# 10_FE_LANPORT.net
KiCad netlist of a schematic drawn in Altium Designer
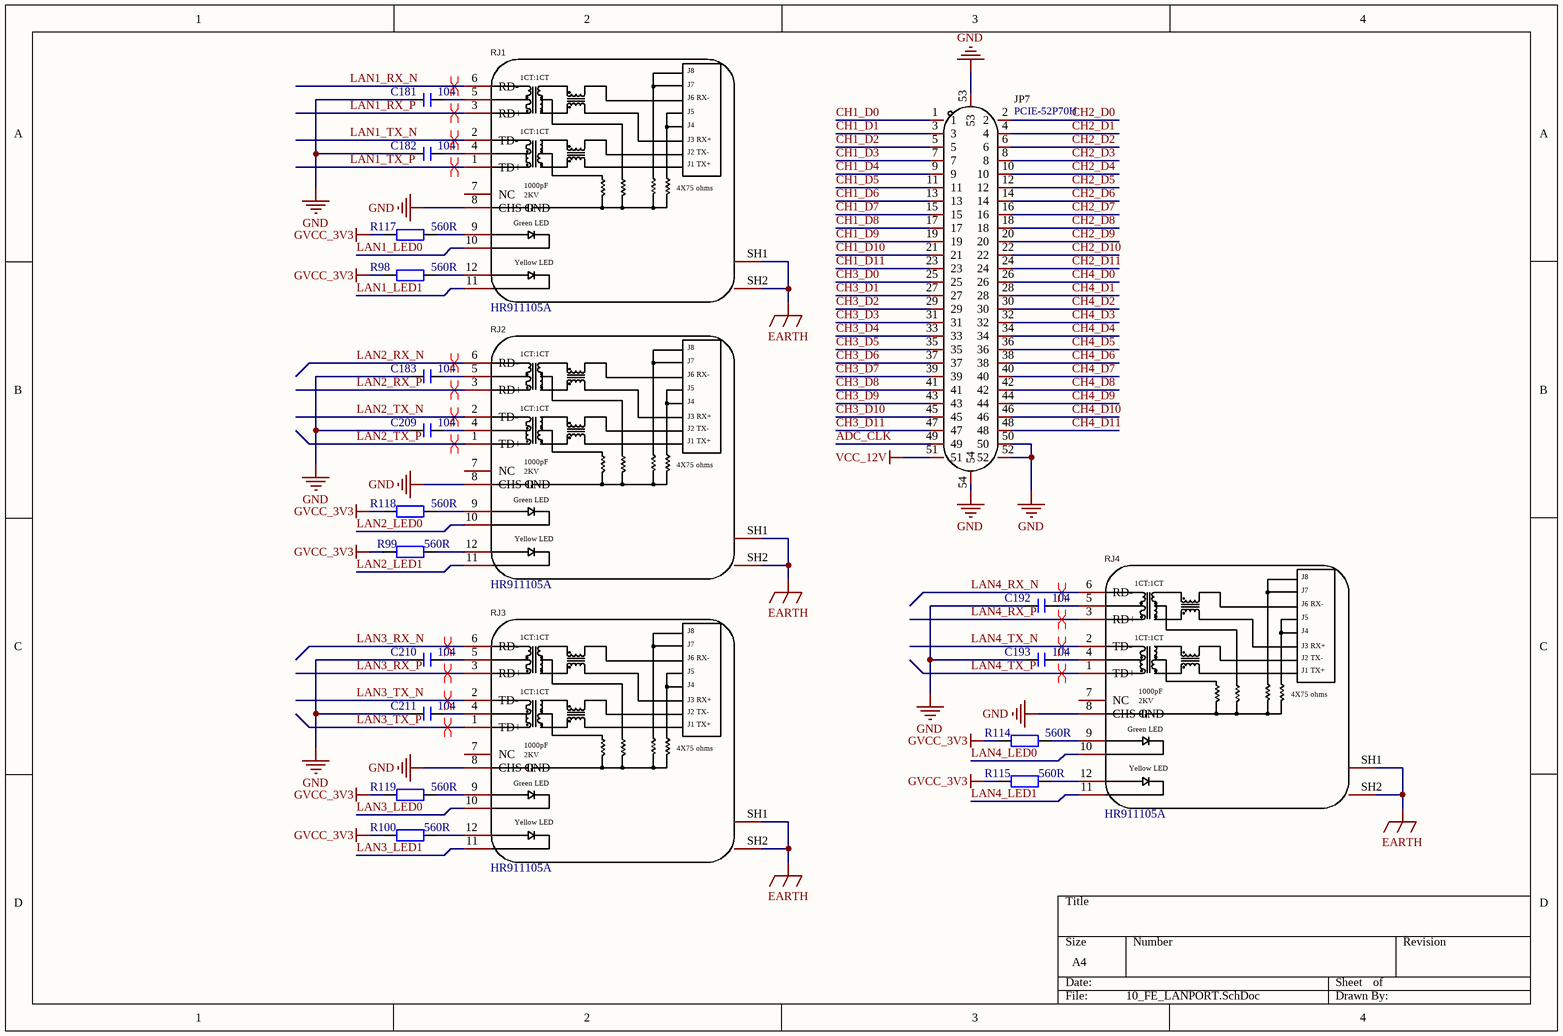
[diagram p0: 10_FE_LANPORT.SchDoc]

(export (version "E")
  (design (tool "Eeschema 10.0.6"))
  (components
    (comp (ref "C181")
      (value "104")
      (footprint "C 0603")
      (description "无极性贴片电容")
      (fields (field (name "版权归属") "源创客"))
      (libsource (lib "STM32MP15x底板封装库V1.4") (part "C"))
    )
    (comp (ref "C182")
      (value "104")
      (footprint "C 0603")
      (description "无极性贴片电容")
      (fields (field (name "版权归属") "源创客"))
      (libsource (lib "STM32MP15x底板封装库V1.4") (part "C"))
    )
    (comp (ref "C183")
      (value "104")
      (footprint "C 0603")
      (description "无极性贴片电容")
      (fields (field (name "版权归属") "源创客"))
      (libsource (lib "STM32MP15x底板封装库V1.4") (part "C"))
    )
    (comp (ref "C192")
      (value "104")
      (footprint "C 0603")
      (description "无极性贴片电容")
      (fields (field (name "版权归属") "源创客"))
      (libsource (lib "STM32MP15x底板封装库V1.4") (part "C"))
    )
    (comp (ref "C193")
      (value "104")
      (footprint "C 0603")
      (description "无极性贴片电容")
      (fields (field (name "版权归属") "源创客"))
      (libsource (lib "STM32MP15x底板封装库V1.4") (part "C"))
    )
    (comp (ref "C209")
      (value "104")
      (footprint "C 0603")
      (description "无极性贴片电容")
      (fields (field (name "版权归属") "源创客"))
      (libsource (lib "STM32MP15x底板封装库V1.4") (part "C"))
    )
    (comp (ref "C210")
      (value "104")
      (footprint "C 0603")
      (description "无极性贴片电容")
      (fields (field (name "版权归属") "源创客"))
      (libsource (lib "STM32MP15x底板封装库V1.4") (part "C"))
    )
    (comp (ref "C211")
      (value "104")
      (footprint "C 0603")
      (description "无极性贴片电容")
      (fields (field (name "版权归属") "源创客"))
      (libsource (lib "STM32MP15x底板封装库V1.4") (part "C"))
    )
    (comp (ref "JP7")
      (value "PCIE-52P70H")
      (footprint "MINI PCIe")
      (fields (field (name "MANUFACTURER") "XUNPU(讯普)"))
      (libsource (lib "PCIE-52P70H") (part "PCIE-52P70H"))
    )
    (comp (ref "R98")
      (value "560R")
      (footprint "R 0603")
      (description "贴片电阻")
      (fields (field (name "版权归属") "源创客"))
      (libsource (lib "STM32MP15x底板封装库V1.4") (part "R"))
    )
    (comp (ref "R99")
      (value "560R")
      (footprint "R 0603")
      (description "贴片电阻")
      (fields (field (name "版权归属") "源创客"))
      (libsource (lib "STM32MP15x底板封装库V1.4") (part "R"))
    )
    (comp (ref "R100")
      (value "560R")
      (footprint "R 0603")
      (description "贴片电阻")
      (fields (field (name "版权归属") "源创客"))
      (libsource (lib "STM32MP15x底板封装库V1.4") (part "R"))
    )
    (comp (ref "R114")
      (value "560R")
      (footprint "R 0603")
      (description "贴片电阻")
      (fields (field (name "版权归属") "源创客"))
      (libsource (lib "STM32MP15x底板封装库V1.4") (part "R"))
    )
    (comp (ref "R115")
      (value "560R")
      (footprint "R 0603")
      (description "贴片电阻")
      (fields (field (name "版权归属") "源创客"))
      (libsource (lib "STM32MP15x底板封装库V1.4") (part "R"))
    )
    (comp (ref "R117")
      (value "560R")
      (footprint "R 0603")
      (description "贴片电阻")
      (fields (field (name "版权归属") "源创客"))
      (libsource (lib "STM32MP15x底板封装库V1.4") (part "R"))
    )
    (comp (ref "R118")
      (value "560R")
      (footprint "R 0603")
      (description "贴片电阻")
      (fields (field (name "版权归属") "源创客"))
      (libsource (lib "STM32MP15x底板封装库V1.4") (part "R"))
    )
    (comp (ref "R119")
      (value "560R")
      (footprint "R 0603")
      (description "贴片电阻")
      (fields (field (name "版权归属") "源创客"))
      (libsource (lib "STM32MP15x底板封装库V1.4") (part "R"))
    )
    (comp (ref "RJ1")
      (value "HR911105A")
      (footprint "HR91105A")
      (fields (field (name "MANUFACTURER") "HANRUN(汉仁)"))
      (libsource (lib "HR911105A") (part "HR911105A"))
    )
    (comp (ref "RJ2")
      (value "HR911105A")
      (footprint "HR91105A")
      (fields (field (name "MANUFACTURER") "HANRUN(汉仁)"))
      (libsource (lib "HR911105A") (part "HR911105A"))
    )
    (comp (ref "RJ3")
      (value "HR911105A")
      (footprint "HR91105A")
      (fields (field (name "MANUFACTURER") "HANRUN(汉仁)"))
      (libsource (lib "HR911105A") (part "HR911105A"))
    )
    (comp (ref "RJ4")
      (value "HR911105A")
      (footprint "HR91105A")
      (fields (field (name "MANUFACTURER") "HANRUN(汉仁)"))
      (libsource (lib "HR911105A") (part "HR911105A"))
    )
  )
  (nets
    (net (code "1") (name "/ADC_CLK") (class "Default")
      (node (ref "JP7") (pin "49") (pinfunction "49_49") (pintype "passive"))
    )
    (net (code "2") (name "/CH1_D0") (class "Default")
      (node (ref "JP7") (pin "1") (pinfunction "1_1") (pintype "passive"))
    )
    (net (code "3") (name "/CH1_D1") (class "Default")
      (node (ref "JP7") (pin "3") (pinfunction "3_3") (pintype "passive"))
    )
    (net (code "4") (name "/CH1_D2") (class "Default")
      (node (ref "JP7") (pin "5") (pinfunction "5_5") (pintype "passive"))
    )
    (net (code "5") (name "/CH1_D3") (class "Default")
      (node (ref "JP7") (pin "7") (pinfunction "7_7") (pintype "passive"))
    )
    (net (code "6") (name "/CH1_D4") (class "Default")
      (node (ref "JP7") (pin "9") (pinfunction "9_9") (pintype "passive"))
    )
    (net (code "7") (name "/CH1_D5") (class "Default")
      (node (ref "JP7") (pin "11") (pinfunction "11_11") (pintype "passive"))
    )
    (net (code "8") (name "/CH1_D6") (class "Default")
      (node (ref "JP7") (pin "13") (pinfunction "13_13") (pintype "passive"))
    )
    (net (code "9") (name "/CH1_D7") (class "Default")
      (node (ref "JP7") (pin "15") (pinfunction "15_15") (pintype "passive"))
    )
    (net (code "10") (name "/CH1_D8") (class "Default")
      (node (ref "JP7") (pin "17") (pinfunction "17_17") (pintype "passive"))
    )
    (net (code "11") (name "/CH1_D9") (class "Default")
      (node (ref "JP7") (pin "19") (pinfunction "19_19") (pintype "passive"))
    )
    (net (code "12") (name "/CH1_D10") (class "Default")
      (node (ref "JP7") (pin "21") (pinfunction "21_21") (pintype "passive"))
    )
    (net (code "13") (name "/CH1_D11") (class "Default")
      (node (ref "JP7") (pin "23") (pinfunction "23_23") (pintype "passive"))
    )
    (net (code "14") (name "/CH2_D0") (class "Default")
      (node (ref "JP7") (pin "2") (pinfunction "2_2") (pintype "passive"))
    )
    (net (code "15") (name "/CH2_D1") (class "Default")
      (node (ref "JP7") (pin "4") (pinfunction "4_4") (pintype "passive"))
    )
    (net (code "16") (name "/CH2_D2") (class "Default")
      (node (ref "JP7") (pin "6") (pinfunction "6_6") (pintype "passive"))
    )
    (net (code "17") (name "/CH2_D3") (class "Default")
      (node (ref "JP7") (pin "8") (pinfunction "8_8") (pintype "passive"))
    )
    (net (code "18") (name "/CH2_D4") (class "Default")
      (node (ref "JP7") (pin "10") (pinfunction "10_10") (pintype "passive"))
    )
    (net (code "19") (name "/CH2_D5") (class "Default")
      (node (ref "JP7") (pin "12") (pinfunction "12_12") (pintype "passive"))
    )
    (net (code "20") (name "/CH2_D6") (class "Default")
      (node (ref "JP7") (pin "14") (pinfunction "14_14") (pintype "passive"))
    )
    (net (code "21") (name "/CH2_D7") (class "Default")
      (node (ref "JP7") (pin "16") (pinfunction "16_16") (pintype "passive"))
    )
    (net (code "22") (name "/CH2_D8") (class "Default")
      (node (ref "JP7") (pin "18") (pinfunction "18_18") (pintype "passive"))
    )
    (net (code "23") (name "/CH2_D9") (class "Default")
      (node (ref "JP7") (pin "20") (pinfunction "20_20") (pintype "passive"))
    )
    (net (code "24") (name "/CH2_D10") (class "Default")
      (node (ref "JP7") (pin "22") (pinfunction "22_22") (pintype "passive"))
    )
    (net (code "25") (name "/CH2_D11") (class "Default")
      (node (ref "JP7") (pin "24") (pinfunction "24_24") (pintype "passive"))
    )
    (net (code "26") (name "/CH3_D0") (class "Default")
      (node (ref "JP7") (pin "25") (pinfunction "25_25") (pintype "passive"))
    )
    (net (code "27") (name "/CH3_D1") (class "Default")
      (node (ref "JP7") (pin "27") (pinfunction "27_27") (pintype "passive"))
    )
    (net (code "28") (name "/CH3_D2") (class "Default")
      (node (ref "JP7") (pin "29") (pinfunction "29_29") (pintype "passive"))
    )
    (net (code "29") (name "/CH3_D3") (class "Default")
      (node (ref "JP7") (pin "31") (pinfunction "31_31") (pintype "passive"))
    )
    (net (code "30") (name "/CH3_D4") (class "Default")
      (node (ref "JP7") (pin "33") (pinfunction "33_33") (pintype "passive"))
    )
    (net (code "31") (name "/CH3_D5") (class "Default")
      (node (ref "JP7") (pin "35") (pinfunction "35_35") (pintype "passive"))
    )
    (net (code "32") (name "/CH3_D6") (class "Default")
      (node (ref "JP7") (pin "37") (pinfunction "37_37") (pintype "passive"))
    )
    (net (code "33") (name "/CH3_D7") (class "Default")
      (node (ref "JP7") (pin "39") (pinfunction "39_39") (pintype "passive"))
    )
    (net (code "34") (name "/CH3_D8") (class "Default")
      (node (ref "JP7") (pin "41") (pinfunction "41_41") (pintype "passive"))
    )
    (net (code "35") (name "/CH3_D9") (class "Default")
      (node (ref "JP7") (pin "43") (pinfunction "43_43") (pintype "passive"))
    )
    (net (code "36") (name "/CH3_D10") (class "Default")
      (node (ref "JP7") (pin "45") (pinfunction "45_45") (pintype "passive"))
    )
    (net (code "37") (name "/CH3_D11") (class "Default")
      (node (ref "JP7") (pin "47") (pinfunction "47_47") (pintype "passive"))
    )
    (net (code "38") (name "/CH4_D0") (class "Default")
      (node (ref "JP7") (pin "26") (pinfunction "26_26") (pintype "passive"))
    )
    (net (code "39") (name "/CH4_D1") (class "Default")
      (node (ref "JP7") (pin "28") (pinfunction "28_28") (pintype "passive"))
    )
    (net (code "40") (name "/CH4_D2") (class "Default")
      (node (ref "JP7") (pin "30") (pinfunction "30_30") (pintype "passive"))
    )
    (net (code "41") (name "/CH4_D3") (class "Default")
      (node (ref "JP7") (pin "32") (pinfunction "32_32") (pintype "passive"))
    )
    (net (code "42") (name "/CH4_D4") (class "Default")
      (node (ref "JP7") (pin "34") (pinfunction "34_34") (pintype "passive"))
    )
    (net (code "43") (name "/CH4_D5") (class "Default")
      (node (ref "JP7") (pin "36") (pinfunction "36_36") (pintype "passive"))
    )
    (net (code "44") (name "/CH4_D6") (class "Default")
      (node (ref "JP7") (pin "38") (pinfunction "38_38") (pintype "passive"))
    )
    (net (code "45") (name "/CH4_D7") (class "Default")
      (node (ref "JP7") (pin "40") (pinfunction "40_40") (pintype "passive"))
    )
    (net (code "46") (name "/CH4_D8") (class "Default")
      (node (ref "JP7") (pin "42") (pinfunction "42_42") (pintype "passive"))
    )
    (net (code "47") (name "/CH4_D9") (class "Default")
      (node (ref "JP7") (pin "44") (pinfunction "44_44") (pintype "passive"))
    )
    (net (code "48") (name "/CH4_D10") (class "Default")
      (node (ref "JP7") (pin "46") (pinfunction "46_46") (pintype "passive"))
    )
    (net (code "49") (name "/CH4_D11") (class "Default")
      (node (ref "JP7") (pin "48") (pinfunction "48_48") (pintype "passive"))
    )
    (net (code "50") (name "/LAN1_LED0") (class "Default")
      (node (ref "RJ1") (pin "10") (pinfunction "10_10") (pintype "passive"))
    )
    (net (code "51") (name "/LAN1_LED1") (class "Default")
      (node (ref "RJ1") (pin "11") (pinfunction "11_11") (pintype "passive"))
    )
    (net (code "52") (name "/LAN1_RX_N") (class "Default")
      (node (ref "RJ1") (pin "6") (pinfunction "RD-_6") (pintype "passive"))
    )
    (net (code "53") (name "/LAN1_RX_P") (class "Default")
      (node (ref "RJ1") (pin "3") (pinfunction "RD+_3") (pintype "passive"))
    )
    (net (code "54") (name "/LAN1_TX_N") (class "Default")
      (node (ref "RJ1") (pin "2") (pinfunction "TD-_2") (pintype "passive"))
    )
    (net (code "55") (name "/LAN1_TX_P") (class "Default")
      (node (ref "RJ1") (pin "1") (pinfunction "TD+_1") (pintype "passive"))
    )
    (net (code "56") (name "/LAN2_LED0") (class "Default")
      (node (ref "RJ2") (pin "10") (pinfunction "10_10") (pintype "passive"))
    )
    (net (code "57") (name "/LAN2_LED1") (class "Default")
      (node (ref "RJ2") (pin "11") (pinfunction "11_11") (pintype "passive"))
    )
    (net (code "58") (name "/LAN2_RX_N") (class "Default")
      (node (ref "RJ2") (pin "6") (pinfunction "RD-_6") (pintype "passive"))
    )
    (net (code "59") (name "/LAN2_RX_P") (class "Default")
      (node (ref "RJ2") (pin "3") (pinfunction "RD+_3") (pintype "passive"))
    )
    (net (code "60") (name "/LAN2_TX_N") (class "Default")
      (node (ref "RJ2") (pin "2") (pinfunction "TD-_2") (pintype "passive"))
    )
    (net (code "61") (name "/LAN2_TX_P") (class "Default")
      (node (ref "RJ2") (pin "1") (pinfunction "TD+_1") (pintype "passive"))
    )
    (net (code "62") (name "/LAN3_LED0") (class "Default")
      (node (ref "RJ3") (pin "10") (pinfunction "10_10") (pintype "passive"))
    )
    (net (code "63") (name "/LAN3_LED1") (class "Default")
      (node (ref "RJ3") (pin "11") (pinfunction "11_11") (pintype "passive"))
    )
    (net (code "64") (name "/LAN3_RX_N") (class "Default")
      (node (ref "RJ3") (pin "6") (pinfunction "RD-_6") (pintype "passive"))
    )
    (net (code "65") (name "/LAN3_RX_P") (class "Default")
      (node (ref "RJ3") (pin "3") (pinfunction "RD+_3") (pintype "passive"))
    )
    (net (code "66") (name "/LAN3_TX_N") (class "Default")
      (node (ref "RJ3") (pin "2") (pinfunction "TD-_2") (pintype "passive"))
    )
    (net (code "67") (name "/LAN3_TX_P") (class "Default")
      (node (ref "RJ3") (pin "1") (pinfunction "TD+_1") (pintype "passive"))
    )
    (net (code "68") (name "/LAN4_LED0") (class "Default")
      (node (ref "RJ4") (pin "10") (pinfunction "10_10") (pintype "passive"))
    )
    (net (code "69") (name "/LAN4_LED1") (class "Default")
      (node (ref "RJ4") (pin "11") (pinfunction "11_11") (pintype "passive"))
    )
    (net (code "70") (name "/LAN4_RX_N") (class "Default")
      (node (ref "RJ4") (pin "6") (pinfunction "RD-_6") (pintype "passive"))
    )
    (net (code "71") (name "/LAN4_RX_P") (class "Default")
      (node (ref "RJ4") (pin "3") (pinfunction "RD+_3") (pintype "passive"))
    )
    (net (code "72") (name "/LAN4_TX_N") (class "Default")
      (node (ref "RJ4") (pin "2") (pinfunction "TD-_2") (pintype "passive"))
    )
    (net (code "73") (name "/LAN4_TX_P") (class "Default")
      (node (ref "RJ4") (pin "1") (pinfunction "TD+_1") (pintype "passive"))
    )
    (net (code "74") (name "EARTH") (class "Default")
      (node (ref "RJ1") (pin "SH1") (pinfunction "SH1_SH1") (pintype "passive"))
      (node (ref "RJ1") (pin "SH2") (pinfunction "SH2_SH2") (pintype "passive"))
      (node (ref "RJ2") (pin "SH1") (pinfunction "SH1_SH1") (pintype "passive"))
      (node (ref "RJ2") (pin "SH2") (pinfunction "SH2_SH2") (pintype "passive"))
      (node (ref "RJ3") (pin "SH1") (pinfunction "SH1_SH1") (pintype "passive"))
      (node (ref "RJ3") (pin "SH2") (pinfunction "SH2_SH2") (pintype "passive"))
      (node (ref "RJ4") (pin "SH1") (pinfunction "SH1_SH1") (pintype "passive"))
      (node (ref "RJ4") (pin "SH2") (pinfunction "SH2_SH2") (pintype "passive"))
    )
    (net (code "75") (name "GND") (class "Default")
      (node (ref "C181") (pin "1") (pinfunction "1_1") (pintype "passive"))
      (node (ref "C182") (pin "2") (pinfunction "2_2") (pintype "passive"))
      (node (ref "C183") (pin "2") (pinfunction "2_2") (pintype "passive"))
      (node (ref "C192") (pin "1") (pinfunction "1_1") (pintype "passive"))
      (node (ref "C193") (pin "1") (pinfunction "1_1") (pintype "passive"))
      (node (ref "C209") (pin "1") (pinfunction "1_1") (pintype "passive"))
      (node (ref "C210") (pin "1") (pinfunction "1_1") (pintype "passive"))
      (node (ref "C211") (pin "1") (pinfunction "1_1") (pintype "passive"))
      (node (ref "JP7") (pin "50") (pinfunction "50_50") (pintype "passive"))
      (node (ref "JP7") (pin "52") (pinfunction "52_52") (pintype "passive"))
      (node (ref "JP7") (pin "53") (pinfunction "53_53") (pintype "passive"))
      (node (ref "JP7") (pin "54") (pinfunction "54_54") (pintype "passive"))
      (node (ref "RJ1") (pin "8") (pinfunction "CHS_GND_8") (pintype "passive"))
      (node (ref "RJ2") (pin "8") (pinfunction "CHS_GND_8") (pintype "passive"))
      (node (ref "RJ3") (pin "8") (pinfunction "CHS_GND_8") (pintype "passive"))
      (node (ref "RJ4") (pin "8") (pinfunction "CHS_GND_8") (pintype "passive"))
    )
    (net (code "76") (name "GVCC_3V3") (class "Default")
      (node (ref "R100") (pin "1") (pinfunction "1_1") (pintype "passive"))
      (node (ref "R114") (pin "2") (pinfunction "2_2") (pintype "passive"))
      (node (ref "R115") (pin "1") (pinfunction "1_1") (pintype "passive"))
      (node (ref "R117") (pin "2") (pinfunction "2_2") (pintype "passive"))
      (node (ref "R118") (pin "2") (pinfunction "2_2") (pintype "passive"))
      (node (ref "R119") (pin "2") (pinfunction "2_2") (pintype "passive"))
      (node (ref "R98") (pin "2") (pinfunction "2_2") (pintype "passive"))
      (node (ref "R99") (pin "1") (pinfunction "1_1") (pintype "passive"))
    )
    (net (code "77") (name "Net-(C181-Pad2)") (class "Default")
      (node (ref "C181") (pin "2") (pinfunction "2_2") (pintype "passive"))
      (node (ref "RJ1") (pin "5") (pinfunction "5_5") (pintype "passive"))
    )
    (net (code "78") (name "Net-(C182-Pad1)") (class "Default")
      (node (ref "C182") (pin "1") (pinfunction "1_1") (pintype "passive"))
      (node (ref "RJ1") (pin "4") (pinfunction "4_4") (pintype "passive"))
    )
    (net (code "79") (name "Net-(C183-Pad1)") (class "Default")
      (node (ref "C183") (pin "1") (pinfunction "1_1") (pintype "passive"))
      (node (ref "RJ2") (pin "5") (pinfunction "5_5") (pintype "passive"))
    )
    (net (code "80") (name "Net-(C192-Pad2)") (class "Default")
      (node (ref "C192") (pin "2") (pinfunction "2_2") (pintype "passive"))
      (node (ref "RJ4") (pin "5") (pinfunction "5_5") (pintype "passive"))
    )
    (net (code "81") (name "Net-(C193-Pad2)") (class "Default")
      (node (ref "C193") (pin "2") (pinfunction "2_2") (pintype "passive"))
      (node (ref "RJ4") (pin "4") (pinfunction "4_4") (pintype "passive"))
    )
    (net (code "82") (name "Net-(C209-Pad2)") (class "Default")
      (node (ref "C209") (pin "2") (pinfunction "2_2") (pintype "passive"))
      (node (ref "RJ2") (pin "4") (pinfunction "4_4") (pintype "passive"))
    )
    (net (code "83") (name "Net-(C210-Pad2)") (class "Default")
      (node (ref "C210") (pin "2") (pinfunction "2_2") (pintype "passive"))
      (node (ref "RJ3") (pin "5") (pinfunction "5_5") (pintype "passive"))
    )
    (net (code "84") (name "Net-(C211-Pad2)") (class "Default")
      (node (ref "C211") (pin "2") (pinfunction "2_2") (pintype "passive"))
      (node (ref "RJ3") (pin "4") (pinfunction "4_4") (pintype "passive"))
    )
    (net (code "85") (name "Net-(R98-Pad1)") (class "Default")
      (node (ref "R98") (pin "1") (pinfunction "1_1") (pintype "passive"))
      (node (ref "RJ1") (pin "12") (pinfunction "12_12") (pintype "passive"))
    )
    (net (code "86") (name "Net-(R99-Pad2)") (class "Default")
      (node (ref "R99") (pin "2") (pinfunction "2_2") (pintype "passive"))
      (node (ref "RJ2") (pin "12") (pinfunction "12_12") (pintype "passive"))
    )
    (net (code "87") (name "Net-(R100-Pad2)") (class "Default")
      (node (ref "R100") (pin "2") (pinfunction "2_2") (pintype "passive"))
      (node (ref "RJ3") (pin "12") (pinfunction "12_12") (pintype "passive"))
    )
    (net (code "88") (name "Net-(R114-Pad1)") (class "Default")
      (node (ref "R114") (pin "1") (pinfunction "1_1") (pintype "passive"))
      (node (ref "RJ4") (pin "9") (pinfunction "9_9") (pintype "passive"))
    )
    (net (code "89") (name "Net-(R115-Pad2)") (class "Default")
      (node (ref "R115") (pin "2") (pinfunction "2_2") (pintype "passive"))
      (node (ref "RJ4") (pin "12") (pinfunction "12_12") (pintype "passive"))
    )
    (net (code "90") (name "Net-(R117-Pad1)") (class "Default")
      (node (ref "R117") (pin "1") (pinfunction "1_1") (pintype "passive"))
      (node (ref "RJ1") (pin "9") (pinfunction "9_9") (pintype "passive"))
    )
    (net (code "91") (name "Net-(R118-Pad1)") (class "Default")
      (node (ref "R118") (pin "1") (pinfunction "1_1") (pintype "passive"))
      (node (ref "RJ2") (pin "9") (pinfunction "9_9") (pintype "passive"))
    )
    (net (code "92") (name "Net-(R119-Pad1)") (class "Default")
      (node (ref "R119") (pin "1") (pinfunction "1_1") (pintype "passive"))
      (node (ref "RJ3") (pin "9") (pinfunction "9_9") (pintype "passive"))
    )
    (net (code "93") (name "VCC_12V") (class "Default")
      (node (ref "JP7") (pin "51") (pinfunction "51_51") (pintype "passive"))
    )
    (net (code "94") (name "unconnected-(RJ1-NC-Pad7)") (class "Default")
      (node (ref "RJ1") (pin "7") (pinfunction "NC_7") (pintype "passive"))
    )
    (net (code "95") (name "unconnected-(RJ2-NC-Pad7)") (class "Default")
      (node (ref "RJ2") (pin "7") (pinfunction "NC_7") (pintype "passive"))
    )
    (net (code "96") (name "unconnected-(RJ3-NC-Pad7)") (class "Default")
      (node (ref "RJ3") (pin "7") (pinfunction "NC_7") (pintype "passive"))
    )
    (net (code "97") (name "unconnected-(RJ4-NC-Pad7)") (class "Default")
      (node (ref "RJ4") (pin "7") (pinfunction "NC_7") (pintype "passive"))
    )
  )
)
